# buttons.net
KiCad netlist of a schematic drawn in EAGLE
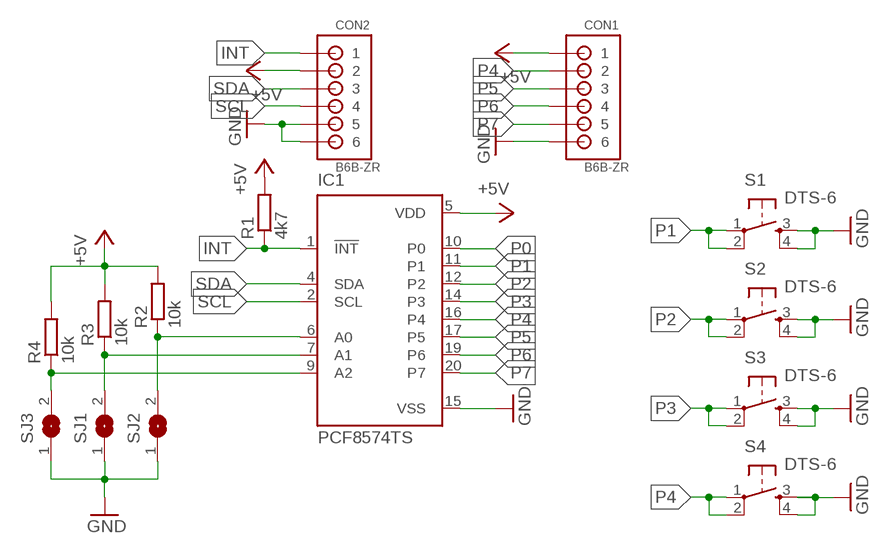
[diagram p0: schematic, sheet 1]

(export (version "E")
  (design (tool "Eeschema 10.0.6"))
  (components
    (comp (ref "CON1")
      (value "B6B-ZR")
      (footprint "eagle-import:B6B-ZR")
      (libsource (lib "eagle-import") (part "B6B-ZR"))
    )
    (comp (ref "CON2")
      (value "B6B-ZR")
      (footprint "eagle-import:B6B-ZR")
      (libsource (lib "eagle-import") (part "B6B-ZR"))
    )
    (comp (ref "IC1")
      (value "PCF8574TS")
      (footprint "eagle-import:SSOP20")
      (fields (field (name "MPN") "PCF8574TS/3,118"))
      (libsource (lib "eagle-import") (part "PCF8574TS"))
    )
    (comp (ref "R1")
      (value "4k7")
      (footprint "eagle-import:R0805")
      (libsource (lib "eagle-import") (part "R-EU_R0805"))
    )
    (comp (ref "R2")
      (value "10k")
      (footprint "eagle-import:R0805")
      (libsource (lib "eagle-import") (part "R-EU_R0805"))
    )
    (comp (ref "R3")
      (value "10k")
      (footprint "eagle-import:R0805")
      (libsource (lib "eagle-import") (part "R-EU_R0805"))
    )
    (comp (ref "R4")
      (value "10k")
      (footprint "eagle-import:R0805")
      (libsource (lib "eagle-import") (part "R-EU_R0805"))
    )
    (comp (ref "S1")
      (value "DTS-6")
      (footprint "eagle-import:DTS-6")
      (libsource (lib "eagle-import") (part "DTS-6"))
    )
    (comp (ref "S2")
      (value "DTS-6")
      (footprint "eagle-import:DTS-6")
      (libsource (lib "eagle-import") (part "DTS-6"))
    )
    (comp (ref "S3")
      (value "DTS-6")
      (footprint "eagle-import:DTS-6")
      (libsource (lib "eagle-import") (part "DTS-6"))
    )
    (comp (ref "S4")
      (value "DTS-6")
      (footprint "eagle-import:DTS-6")
      (libsource (lib "eagle-import") (part "DTS-6"))
    )
    (comp (ref "SJ1") (value "SJ") (footprint "eagle-import:SJ") (libsource (lib "eagle-import") (part "SJ")))
    (comp (ref "SJ2") (value "SJ") (footprint "eagle-import:SJ") (libsource (lib "eagle-import") (part "SJ")))
    (comp (ref "SJ3") (value "SJ") (footprint "eagle-import:SJ") (libsource (lib "eagle-import") (part "SJ")))
  )
  (nets
    (net (code "1") (name "+5V") (class "Default")
      (node (ref "CON1") (pin "1") (pinfunction "1_1") (pintype "bidirectional"))
      (node (ref "CON2") (pin "2") (pinfunction "2_2") (pintype "bidirectional"))
      (node (ref "IC1") (pin "5") (pinfunction "VDD_5") (pintype "power_in"))
      (node (ref "R1") (pin "2") (pinfunction "2_2") (pintype "passive"))
      (node (ref "R2") (pin "2") (pinfunction "2_2") (pintype "passive"))
      (node (ref "R3") (pin "2") (pinfunction "2_2") (pintype "passive"))
      (node (ref "R4") (pin "2") (pinfunction "2_2") (pintype "passive"))
    )
    (net (code "2") (name "GND") (class "Default")
      (node (ref "CON1") (pin "6") (pinfunction "6_6") (pintype "bidirectional"))
      (node (ref "CON2") (pin "5") (pinfunction "5_5") (pintype "bidirectional"))
      (node (ref "CON2") (pin "6") (pinfunction "6_6") (pintype "bidirectional"))
      (node (ref "IC1") (pin "15") (pinfunction "VSS_15") (pintype "power_in"))
      (node (ref "S1") (pin "3") (pinfunction "3_3") (pintype "passive"))
      (node (ref "S1") (pin "4") (pinfunction "4_4") (pintype "passive"))
      (node (ref "S2") (pin "3") (pinfunction "3_3") (pintype "passive"))
      (node (ref "S2") (pin "4") (pinfunction "4_4") (pintype "passive"))
      (node (ref "S3") (pin "3") (pinfunction "3_3") (pintype "passive"))
      (node (ref "S3") (pin "4") (pinfunction "4_4") (pintype "passive"))
      (node (ref "S4") (pin "3") (pinfunction "3_3") (pintype "passive"))
      (node (ref "S4") (pin "4") (pinfunction "4_4") (pintype "passive"))
      (node (ref "SJ1") (pin "1") (pinfunction "1_1") (pintype "passive"))
      (node (ref "SJ2") (pin "1") (pinfunction "1_1") (pintype "passive"))
      (node (ref "SJ3") (pin "1") (pinfunction "1_1") (pintype "passive"))
    )
    (net (code "3") (name "INT") (class "Default")
      (node (ref "CON2") (pin "1") (pinfunction "1_1") (pintype "bidirectional"))
      (node (ref "IC1") (pin "1") (pinfunction "~{INT}_1") (pintype "output"))
      (node (ref "R1") (pin "1") (pinfunction "1_1") (pintype "passive"))
    )
    (net (code "4") (name "Net-(IC1-A0)") (class "Default")
      (node (ref "IC1") (pin "6") (pinfunction "A0_6") (pintype "input"))
      (node (ref "R2") (pin "1") (pinfunction "1_1") (pintype "passive"))
      (node (ref "SJ2") (pin "2") (pinfunction "2_2") (pintype "passive"))
    )
    (net (code "5") (name "Net-(IC1-A1)") (class "Default")
      (node (ref "IC1") (pin "7") (pinfunction "A1_7") (pintype "input"))
      (node (ref "R3") (pin "1") (pinfunction "1_1") (pintype "passive"))
      (node (ref "SJ1") (pin "2") (pinfunction "2_2") (pintype "passive"))
    )
    (net (code "6") (name "Net-(IC1-A2)") (class "Default")
      (node (ref "IC1") (pin "9") (pinfunction "A2_9") (pintype "input"))
      (node (ref "R4") (pin "1") (pinfunction "1_1") (pintype "passive"))
      (node (ref "SJ3") (pin "2") (pinfunction "2_2") (pintype "passive"))
    )
    (net (code "7") (name "P0") (class "Default")
      (node (ref "IC1") (pin "10") (pinfunction "P0_10") (pintype "bidirectional"))
    )
    (net (code "8") (name "P1") (class "Default")
      (node (ref "IC1") (pin "11") (pinfunction "P1_11") (pintype "bidirectional"))
      (node (ref "S1") (pin "1") (pinfunction "1_1") (pintype "passive"))
      (node (ref "S1") (pin "2") (pinfunction "2_2") (pintype "passive"))
    )
    (net (code "9") (name "P2") (class "Default")
      (node (ref "IC1") (pin "12") (pinfunction "P2_12") (pintype "bidirectional"))
      (node (ref "S2") (pin "1") (pinfunction "1_1") (pintype "passive"))
      (node (ref "S2") (pin "2") (pinfunction "2_2") (pintype "passive"))
    )
    (net (code "10") (name "P3") (class "Default")
      (node (ref "IC1") (pin "14") (pinfunction "P3_14") (pintype "bidirectional"))
      (node (ref "S3") (pin "1") (pinfunction "1_1") (pintype "passive"))
      (node (ref "S3") (pin "2") (pinfunction "2_2") (pintype "passive"))
    )
    (net (code "11") (name "P4") (class "Default")
      (node (ref "CON1") (pin "2") (pinfunction "2_2") (pintype "bidirectional"))
      (node (ref "IC1") (pin "16") (pinfunction "P4_16") (pintype "bidirectional"))
      (node (ref "S4") (pin "1") (pinfunction "1_1") (pintype "passive"))
      (node (ref "S4") (pin "2") (pinfunction "2_2") (pintype "passive"))
    )
    (net (code "12") (name "P5") (class "Default")
      (node (ref "CON1") (pin "3") (pinfunction "3_3") (pintype "bidirectional"))
      (node (ref "IC1") (pin "17") (pinfunction "P5_17") (pintype "bidirectional"))
    )
    (net (code "13") (name "P6") (class "Default")
      (node (ref "CON1") (pin "4") (pinfunction "4_4") (pintype "bidirectional"))
      (node (ref "IC1") (pin "19") (pinfunction "P6_19") (pintype "bidirectional"))
    )
    (net (code "14") (name "P7") (class "Default")
      (node (ref "CON1") (pin "5") (pinfunction "5_5") (pintype "bidirectional"))
      (node (ref "IC1") (pin "20") (pinfunction "P7_20") (pintype "bidirectional"))
    )
    (net (code "15") (name "SCL") (class "Default")
      (node (ref "CON2") (pin "4") (pinfunction "4_4") (pintype "bidirectional"))
      (node (ref "IC1") (pin "2") (pinfunction "SCL_2") (pintype "input"))
    )
    (net (code "16") (name "SDA") (class "Default")
      (node (ref "CON2") (pin "3") (pinfunction "3_3") (pintype "bidirectional"))
      (node (ref "IC1") (pin "4") (pinfunction "SDA_4") (pintype "bidirectional"))
    )
  )
)
